# ElnC_PeakDetector_BO6.net
KiCad netlist of a schematic drawn in Altium Designer
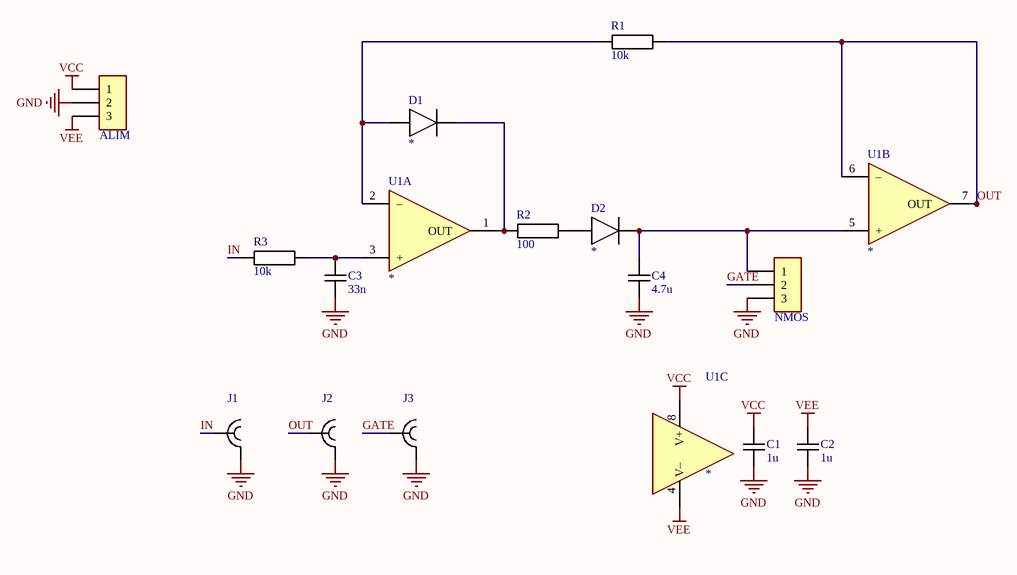
[diagram p0: ElnC_PeakDetector_BO6.SchDoc]

(export (version "E")
  (design (tool "Eeschema 10.0.6"))
  (components
    (comp (ref "ALIM")
      (value "*")
      (footprint "PinHeader1x3 P2.54")
      (description "Plug connector")
      (libsource (lib "PinHeader") (part "PinHeader1x3"))
    )
    (comp (ref "C1")
      (value "1u")
      (footprint "CAPACITOR 2012 REFLOW")
      (description "Capacitor")
      (libsource (lib "Capacitor") (part "Capacitor"))
    )
    (comp (ref "C2")
      (value "1u")
      (footprint "CAPACITOR 2012 REFLOW")
      (description "Capacitor")
      (libsource (lib "Capacitor") (part "Capacitor"))
    )
    (comp (ref "C3")
      (value "33n")
      (footprint "CAPACITOR 2012 REFLOW")
      (description "Capacitor")
      (libsource (lib "Capacitor") (part "Capacitor"))
    )
    (comp (ref "C4")
      (value "4.7u")
      (footprint "CAPACITOR 2012 REFLOW")
      (description "Capacitor")
      (libsource (lib "Capacitor") (part "Capacitor"))
    )
    (comp (ref "D1")
      (value "*")
      (footprint "DIODE D5.4 L10.0 P15.0")
      (description "Diode generic 2 leads")
      (libsource (lib "Diode") (part "DIODE"))
    )
    (comp (ref "D2")
      (value "*")
      (footprint "DIODE D5.4 L10.0 P15.0")
      (description "Diode generic 2 leads")
      (libsource (lib "Diode") (part "DIODE"))
    )
    (comp (ref "J1")
      (value "*")
      (footprint "BNC TH RIGHT ANGLE TE CONNECTIVITY 1-1337543-0")
      (description "BNC")
      (libsource (lib "Connector") (part "BNC"))
    )
    (comp (ref "J2")
      (value "*")
      (footprint "BNC TH RIGHT ANGLE TE CONNECTIVITY 1-1337543-0")
      (description "BNC")
      (libsource (lib "Connector") (part "BNC"))
    )
    (comp (ref "J3")
      (value "*")
      (footprint "BNC TH RIGHT ANGLE TE CONNECTIVITY 1-1337543-0")
      (description "BNC")
      (libsource (lib "Connector") (part "BNC"))
    )
    (comp (ref "NMOS")
      (value "*")
      (footprint "PinHeader1x3 P2.54")
      (description "Plug connector")
      (libsource (lib "PinHeader") (part "PinHeader1x3"))
    )
    (comp (ref "R1")
      (value "10k")
      (footprint "RESISTOR 2012 REFLOW")
      (description "Resistor")
      (libsource (lib "Resistor") (part "Resistor"))
    )
    (comp (ref "R2")
      (value "100")
      (footprint "RESISTOR 2012 REFLOW")
      (description "Resistor")
      (libsource (lib "Resistor") (part "Resistor"))
    )
    (comp (ref "R3")
      (value "10k")
      (footprint "RESISTOR 2012 REFLOW")
      (description "Resistor")
      (libsource (lib "Resistor") (part "Resistor"))
    )
    (comp (ref "U1")
      (value "*")
      (footprint "DIP8 P2.54 W7.62 H5.0")
      (description "Generic dual OPA 8 pins")
      (libsource (lib "Amplifier") (part "OPA DUAL"))
    )
  )
  (nets
    (net (code "1") (name "/GATE") (class "Default")
      (node (ref "J3") (pin "1") (pinfunction "1_1") (pintype "passive"))
      (node (ref "NMOS") (pin "2") (pinfunction "2_2") (pintype "passive"))
    )
    (net (code "2") (name "/IN") (class "Default")
      (node (ref "J1") (pin "1") (pinfunction "1_1") (pintype "passive"))
      (node (ref "R3") (pin "2") (pinfunction "2_2") (pintype "passive"))
    )
    (net (code "3") (name "/OUT") (class "Default")
      (node (ref "J2") (pin "1") (pinfunction "1_1") (pintype "passive"))
      (node (ref "R1") (pin "1") (pinfunction "1_1") (pintype "passive"))
      (node (ref "U1") (pin "6") (pinfunction "–_6") (pintype "passive"))
      (node (ref "U1") (pin "7") (pinfunction "OUT_7") (pintype "passive"))
    )
    (net (code "4") (name "GND") (class "Default")
      (node (ref "ALIM") (pin "2") (pinfunction "2_2") (pintype "passive"))
      (node (ref "C1") (pin "2") (pinfunction "2_2") (pintype "passive"))
      (node (ref "C2") (pin "2") (pinfunction "2_2") (pintype "passive"))
      (node (ref "C3") (pin "2") (pinfunction "2_2") (pintype "passive"))
      (node (ref "C4") (pin "2") (pinfunction "2_2") (pintype "passive"))
      (node (ref "J1") (pin "2") (pinfunction "2_2") (pintype "passive"))
      (node (ref "J2") (pin "2") (pinfunction "2_2") (pintype "passive"))
      (node (ref "J3") (pin "2") (pinfunction "2_2") (pintype "passive"))
      (node (ref "NMOS") (pin "3") (pinfunction "3_3") (pintype "passive"))
    )
    (net (code "5") (name "Net-(D1-A)") (class "Default")
      (node (ref "D1") (pin "2") (pinfunction "A_2") (pintype "passive"))
      (node (ref "R1") (pin "2") (pinfunction "2_2") (pintype "passive"))
      (node (ref "U1") (pin "2") (pinfunction "–_2") (pintype "passive"))
    )
    (net (code "6") (name "Net-(D1-C)") (class "Default")
      (node (ref "D1") (pin "1") (pinfunction "C_1") (pintype "passive"))
      (node (ref "R2") (pin "2") (pinfunction "2_2") (pintype "passive"))
      (node (ref "U1") (pin "1") (pinfunction "OUT_1") (pintype "passive"))
    )
    (net (code "7") (name "Net-(D2-A)") (class "Default")
      (node (ref "D2") (pin "2") (pinfunction "A_2") (pintype "passive"))
      (node (ref "R2") (pin "1") (pinfunction "1_1") (pintype "passive"))
    )
    (net (code "8") (name "Net-(D2-C)") (class "Default")
      (node (ref "C4") (pin "1") (pinfunction "1_1") (pintype "passive"))
      (node (ref "D2") (pin "1") (pinfunction "C_1") (pintype "passive"))
      (node (ref "NMOS") (pin "1") (pinfunction "1_1") (pintype "passive"))
      (node (ref "U1") (pin "5") (pinfunction "+_5") (pintype "passive"))
    )
    (net (code "9") (name "Net-(U1A-+)") (class "Default")
      (node (ref "C3") (pin "1") (pinfunction "1_1") (pintype "passive"))
      (node (ref "R3") (pin "1") (pinfunction "1_1") (pintype "passive"))
      (node (ref "U1") (pin "3") (pinfunction "+_3") (pintype "passive"))
    )
    (net (code "10") (name "VCC") (class "Default")
      (node (ref "ALIM") (pin "1") (pinfunction "1_1") (pintype "passive"))
      (node (ref "C1") (pin "1") (pinfunction "1_1") (pintype "passive"))
      (node (ref "U1") (pin "8") (pinfunction "V+_8") (pintype "passive"))
    )
    (net (code "11") (name "VEE") (class "Default")
      (node (ref "ALIM") (pin "3") (pinfunction "3_3") (pintype "passive"))
      (node (ref "C2") (pin "1") (pinfunction "1_1") (pintype "passive"))
      (node (ref "U1") (pin "4") (pinfunction "V–_4") (pintype "passive"))
    )
  )
)
